# Sheet1.net
KiCad netlist of a schematic drawn in Altium Designer
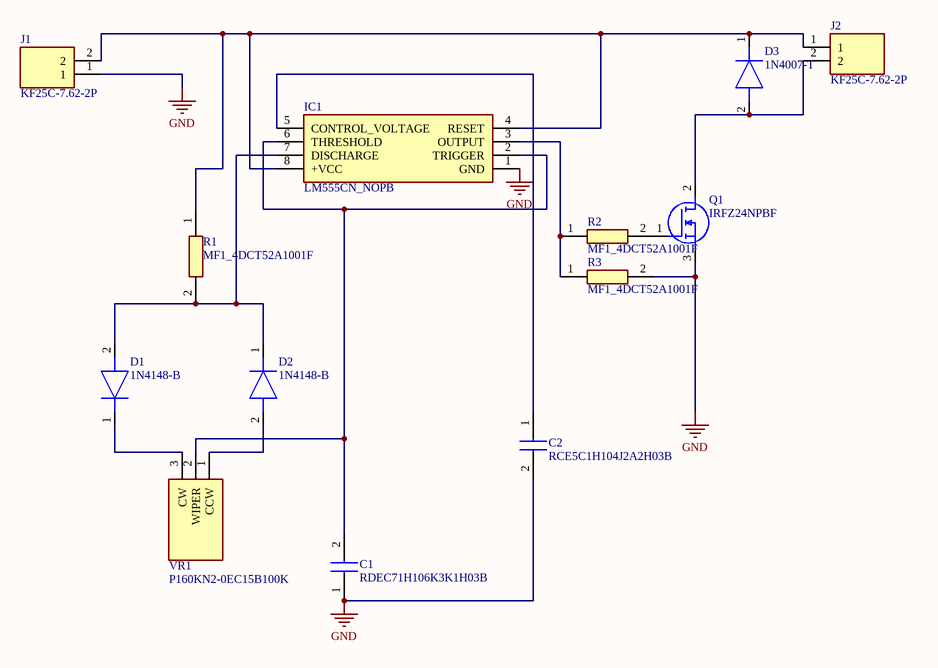
[diagram p0: Sheet1.SchDoc]

(export (version "E")
  (design (tool "Eeschema 10.0.6"))
  (components
    (comp (ref "C1")
      (value "RDEC71H106K3K1H03B")
      (footprint "SamacSys:RDEC71H106K3K1H03B")
      (description "Capacitor")
      (fields (field (name "MOUSER PART NUMBER") "81-RDEC71H106K3K1H3B"))
      (libsource (lib "*") (part "RDEC71H106K3K1H03B"))
    )
    (comp (ref "C2")
      (value "RCE5C1H104J2A2H03B")
      (footprint "SamacSys:RCE5C1H104J2A2H03B")
      (description "Capacitor")
      (fields (field (name "MOUSER PART NUMBER") "81-RCE5C1H104J2A2H3B"))
      (libsource (lib "*") (part "RCE5C1H104J2A2H03B"))
    )
    (comp (ref "D1")
      (value "1N4148-B")
      (footprint "SamacSys:DIOAD1220W56L420D200")
      (description "Diode")
      (fields (field (name "MOUSER PART NUMBER") "583-1N4148-B"))
      (libsource (lib "*") (part "1N4148-B"))
    )
    (comp (ref "D2")
      (value "1N4148-B")
      (footprint "SamacSys:DIOAD1220W56L420D200")
      (description "Diode")
      (fields (field (name "MOUSER PART NUMBER") "583-1N4148-B"))
      (libsource (lib "*") (part "1N4148-B"))
    )
    (comp (ref "D3")
      (value "1N4007-T")
      (footprint "SamacSys:DIOAD1408W86L464D236")
      (description "Diode")
      (fields (field (name "MOUSER PART NUMBER") "621-1N4007"))
      (libsource (lib "*") (part "1N4007-T"))
    )
    (comp (ref "IC1")
      (value "LM555CN_NOPB")
      (footprint "SamacSys:DIP794W53P254L959H508Q8N")
      (description "Integrated Circuit")
      (fields
        (field (name "MANUFACTURER_PART_NUMBER") "LM555CN/NOPB")
        (field (name "MOUSER PART NUMBER") "926-LM555CN/NOPB")
      )
      (libsource (lib "*") (part "LM555CN_NOPB"))
    )
    (comp (ref "J1")
      (value "KF25C-7.62-2P")
      (footprint "SamacSys:KF25C7622P")
      (description "Connector")
      (libsource (lib "") (part "KF25C-7.62-2P_1"))
    )
    (comp (ref "J2")
      (value "KF25C-7.62-2P")
      (footprint "SamacSys:KF25C7622P")
      (description "Connector")
      (libsource (lib "SamacSys") (part "KF25C-7.62-2P"))
    )
    (comp (ref "Q1")
      (value "IRFZ24NPBF")
      (footprint "SamacSys:TO254P469X1042X1967-3P")
      (description "MOSFET (N-Channel)")
      (fields (field (name "MOUSER PART NUMBER") "942-IRFZ24NPBF"))
      (libsource (lib "*") (part "IRFZ24NPBF"))
    )
    (comp (ref "R1")
      (value "MF1_4DCT52A1001F")
      (footprint "SamacSys:RESAD1630W60L710D230")
      (description "Resistor")
      (fields
        (field (name "MANUFACTURER_PART_NUMBER") "MF1/4DCT52A1001F")
        (field (name "MOUSER PART NUMBER") "660-MF1/4DCT52A1001F")
      )
      (libsource (lib "") (part "MF1_4DCT52A1001F_1"))
    )
    (comp (ref "R2")
      (value "MF1_4DCT52A1001F")
      (footprint "SamacSys:RESAD1630W60L710D230")
      (description "Resistor")
      (fields
        (field (name "MANUFACTURER_PART_NUMBER") "MF1/4DCT52A1001F")
        (field (name "MOUSER PART NUMBER") "660-MF1/4DCT52A1001F")
      )
      (libsource (lib "*") (part "MF1_4DCT52A1001F"))
    )
    (comp (ref "R3")
      (value "MF1_4DCT52A1001F")
      (footprint "SamacSys:RESAD1630W60L710D230")
      (description "Resistor")
      (fields
        (field (name "MANUFACTURER_PART_NUMBER") "MF1/4DCT52A1001F")
        (field (name "MOUSER PART NUMBER") "660-MF1/4DCT52A1001F")
      )
      (libsource (lib "*") (part "MF1_4DCT52A1001F"))
    )
    (comp (ref "VR1")
      (value "P160KN2-0EC15B100K")
      (footprint "SamacSys:P160KN20EC15B100K")
      (description "Variable Resistor")
      (fields (field (name "MOUSER PART NUMBER") "858-P160KN20C15B100K"))
      (libsource (lib "*") (part "P160KN2-0EC15B100K"))
    )
  )
  (nets
    (net (code "1") (name "GND") (class "Default")
      (node (ref "C1") (pin "1") (pinfunction "1_1") (pintype "passive"))
      (node (ref "C2") (pin "2") (pinfunction "2_2") (pintype "passive"))
      (node (ref "IC1") (pin "1") (pinfunction "GND_1") (pintype "passive"))
      (node (ref "J1") (pin "1") (pinfunction "1_1") (pintype "passive"))
      (node (ref "Q1") (pin "3") (pinfunction "S_3") (pintype "passive"))
      (node (ref "R3") (pin "2") (pinfunction "2_2") (pintype "passive"))
    )
    (net (code "2") (name "Net-(D1-A)") (class "Default")
      (node (ref "D1") (pin "2") (pinfunction "A_2") (pintype "passive"))
      (node (ref "D2") (pin "1") (pinfunction "K_1") (pintype "passive"))
      (node (ref "IC1") (pin "7") (pinfunction "DISCHARGE_7") (pintype "passive"))
      (node (ref "R1") (pin "2") (pinfunction "2_2") (pintype "passive"))
    )
    (net (code "3") (name "Net-(D1-K)") (class "Default")
      (node (ref "D1") (pin "1") (pinfunction "K_1") (pintype "passive"))
      (node (ref "VR1") (pin "3") (pinfunction "CW_3") (pintype "passive"))
    )
    (net (code "4") (name "Net-(D2-A)") (class "Default")
      (node (ref "D2") (pin "2") (pinfunction "A_2") (pintype "passive"))
      (node (ref "VR1") (pin "1") (pinfunction "CCW_1") (pintype "passive"))
    )
    (net (code "5") (name "Net-(D3-A)") (class "Default")
      (node (ref "D3") (pin "2") (pinfunction "A_2") (pintype "passive"))
      (node (ref "J2") (pin "2") (pinfunction "2_2") (pintype "passive"))
      (node (ref "Q1") (pin "2") (pinfunction "D_2") (pintype "passive"))
    )
    (net (code "6") (name "Net-(D3-K)") (class "Default")
      (node (ref "D3") (pin "1") (pinfunction "K_1") (pintype "passive"))
      (node (ref "IC1") (pin "4") (pinfunction "RESET_4") (pintype "passive"))
      (node (ref "IC1") (pin "8") (pinfunction "+VCC_8") (pintype "passive"))
      (node (ref "J1") (pin "2") (pinfunction "2_2") (pintype "passive"))
      (node (ref "J2") (pin "1") (pinfunction "1_1") (pintype "passive"))
      (node (ref "R1") (pin "1") (pinfunction "1_1") (pintype "passive"))
    )
    (net (code "7") (name "Net-(IC1-CONTROL_VOLTAGE)") (class "Default")
      (node (ref "C2") (pin "1") (pinfunction "1_1") (pintype "passive"))
      (node (ref "IC1") (pin "5") (pinfunction "CONTROL_VOLTAGE_5") (pintype "passive"))
    )
    (net (code "8") (name "Net-(IC1-OUTPUT)") (class "Default")
      (node (ref "IC1") (pin "3") (pinfunction "OUTPUT_3") (pintype "passive"))
      (node (ref "R2") (pin "1") (pinfunction "1_1") (pintype "passive"))
      (node (ref "R3") (pin "1") (pinfunction "1_1") (pintype "passive"))
    )
    (net (code "9") (name "Net-(IC1-THRESHOLD)") (class "Default")
      (node (ref "C1") (pin "2") (pinfunction "2_2") (pintype "passive"))
      (node (ref "IC1") (pin "2") (pinfunction "TRIGGER_2") (pintype "passive"))
      (node (ref "IC1") (pin "6") (pinfunction "THRESHOLD_6") (pintype "passive"))
      (node (ref "VR1") (pin "2") (pinfunction "WIPER_2") (pintype "passive"))
    )
    (net (code "10") (name "Net-(Q1-G)") (class "Default")
      (node (ref "Q1") (pin "1") (pinfunction "G_1") (pintype "passive"))
      (node (ref "R2") (pin "2") (pinfunction "2_2") (pintype "passive"))
    )
  )
)
